# Temp_Sensor.net
KiCad netlist of a schematic drawn in EAGLE
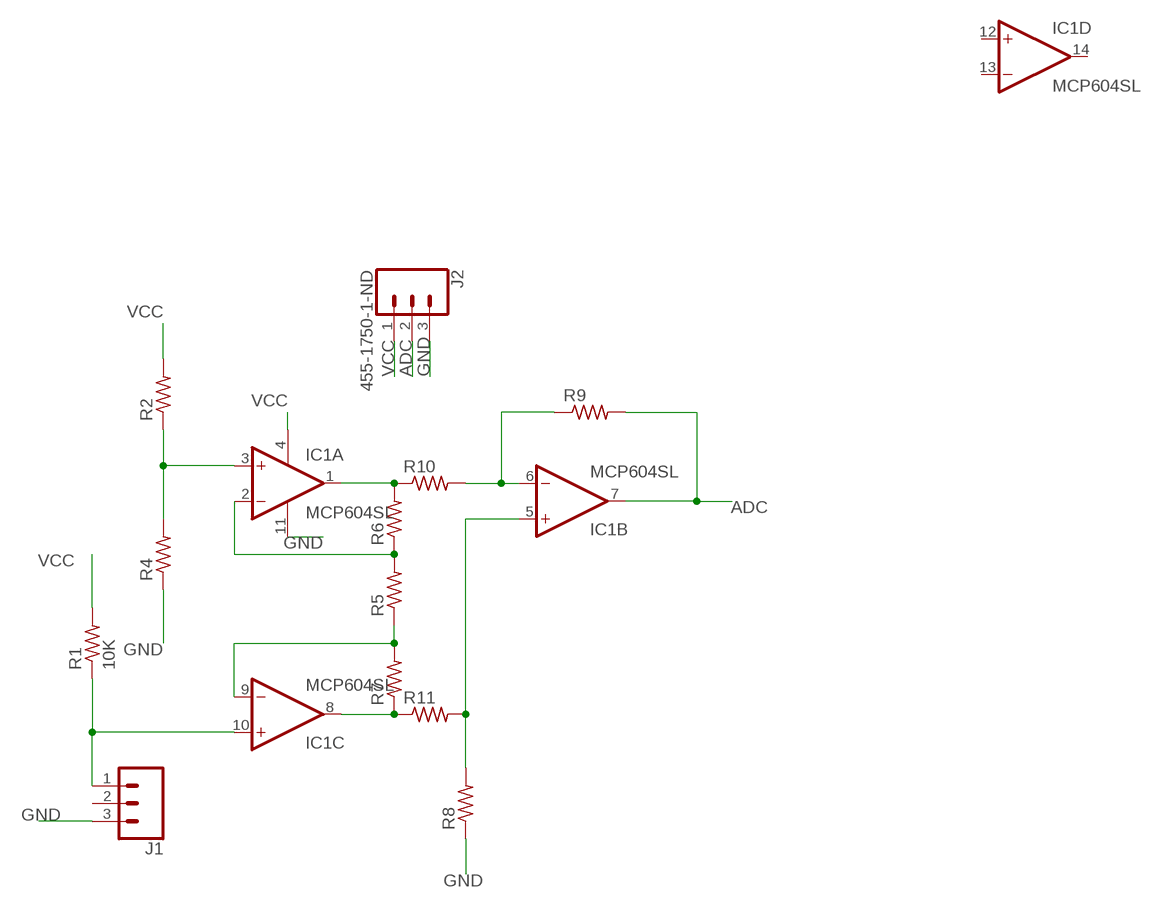
[diagram p0: schematic, sheet 1]

(export (version "E")
  (design (tool "Eeschema 10.0.6"))
  (components
    (comp (ref "IC1")
      (value "MCP604SL")
      (footprint "eagle-import:SO14")
      (libsource (lib "eagle-import") (part "MCP604SL"))
    )
    (comp (ref "J1")
      (value "CONN_03SCREW_LOCK")
      (footprint "eagle-import:SCREWTERMINAL-3.5MM-3_LOCK.007S")
      (libsource (lib "eagle-import") (part "CONN_03SCREW_LOCK"))
    )
    (comp (ref "J2")
      (value "455-1750-1-ND")
      (footprint "eagle-import:1X03")
      (libsource (lib "eagle-import") (part "CONN_03"))
    )
    (comp (ref "R1")
      (value "10K")
      (footprint "eagle-import:R0603")
      (libsource (lib "eagle-import") (part "R-US_R0603"))
    )
    (comp (ref "R2")
      (value "R-US_R0603")
      (footprint "eagle-import:R0603")
      (libsource (lib "eagle-import") (part "R-US_R0603"))
    )
    (comp (ref "R4")
      (value "R-US_R0603")
      (footprint "eagle-import:R0603")
      (libsource (lib "eagle-import") (part "R-US_R0603"))
    )
    (comp (ref "R5")
      (value "R-US_R0603")
      (footprint "eagle-import:R0603")
      (libsource (lib "eagle-import") (part "R-US_R0603"))
    )
    (comp (ref "R6")
      (value "R-US_R0603")
      (footprint "eagle-import:R0603")
      (libsource (lib "eagle-import") (part "R-US_R0603"))
    )
    (comp (ref "R7")
      (value "R-US_R0603")
      (footprint "eagle-import:R0603")
      (libsource (lib "eagle-import") (part "R-US_R0603"))
    )
    (comp (ref "R8")
      (value "R-US_R0603")
      (footprint "eagle-import:R0603")
      (libsource (lib "eagle-import") (part "R-US_R0603"))
    )
    (comp (ref "R9")
      (value "R-US_R0603")
      (footprint "eagle-import:R0603")
      (libsource (lib "eagle-import") (part "R-US_R0603"))
    )
    (comp (ref "R10")
      (value "R-US_R0603")
      (footprint "eagle-import:R0603")
      (libsource (lib "eagle-import") (part "R-US_R0603"))
    )
    (comp (ref "R11")
      (value "R-US_R0603")
      (footprint "eagle-import:R0603")
      (libsource (lib "eagle-import") (part "R-US_R0603"))
    )
  )
  (nets
    (net (code "1") (name "/ADC") (class "Default")
      (node (ref "IC1") (pin "7") (pinfunction "OUT_7") (pintype "output"))
      (node (ref "J2") (pin "2") (pinfunction "2_2") (pintype "passive"))
      (node (ref "R9") (pin "2") (pinfunction "2_2") (pintype "passive"))
    )
    (net (code "2") (name "/GND") (class "Default")
      (node (ref "IC1") (pin "11") (pinfunction "V-_11") (pintype "power_in"))
      (node (ref "J1") (pin "3") (pinfunction "3_3") (pintype "passive"))
      (node (ref "J2") (pin "3") (pinfunction "3_3") (pintype "passive"))
      (node (ref "R4") (pin "1") (pinfunction "1_1") (pintype "passive"))
      (node (ref "R8") (pin "1") (pinfunction "1_1") (pintype "passive"))
    )
    (net (code "3") (name "/VCC") (class "Default")
      (node (ref "IC1") (pin "4") (pinfunction "V+_4") (pintype "power_in"))
      (node (ref "J2") (pin "1") (pinfunction "1_1") (pintype "passive"))
      (node (ref "R1") (pin "2") (pinfunction "2_2") (pintype "passive"))
      (node (ref "R2") (pin "2") (pinfunction "2_2") (pintype "passive"))
    )
    (net (code "4") (name "Net-(IC1A-+IN)") (class "Default")
      (node (ref "IC1") (pin "3") (pinfunction "+IN_3") (pintype "input"))
      (node (ref "R2") (pin "1") (pinfunction "1_1") (pintype "passive"))
      (node (ref "R4") (pin "2") (pinfunction "2_2") (pintype "passive"))
    )
    (net (code "5") (name "Net-(IC1A--IN)") (class "Default")
      (node (ref "IC1") (pin "2") (pinfunction "-IN_2") (pintype "input"))
      (node (ref "R5") (pin "2") (pinfunction "2_2") (pintype "passive"))
      (node (ref "R6") (pin "1") (pinfunction "1_1") (pintype "passive"))
    )
    (net (code "6") (name "Net-(IC1A-OUT)") (class "Default")
      (node (ref "IC1") (pin "1") (pinfunction "OUT_1") (pintype "output"))
      (node (ref "R10") (pin "1") (pinfunction "1_1") (pintype "passive"))
      (node (ref "R6") (pin "2") (pinfunction "2_2") (pintype "passive"))
    )
    (net (code "7") (name "Net-(IC1B-+IN)") (class "Default")
      (node (ref "IC1") (pin "5") (pinfunction "+IN_5") (pintype "input"))
      (node (ref "R11") (pin "2") (pinfunction "2_2") (pintype "passive"))
      (node (ref "R8") (pin "2") (pinfunction "2_2") (pintype "passive"))
    )
    (net (code "8") (name "Net-(IC1B--IN)") (class "Default")
      (node (ref "IC1") (pin "6") (pinfunction "-IN_6") (pintype "input"))
      (node (ref "R10") (pin "2") (pinfunction "2_2") (pintype "passive"))
      (node (ref "R9") (pin "1") (pinfunction "1_1") (pintype "passive"))
    )
    (net (code "9") (name "Net-(IC1C-+IN)") (class "Default")
      (node (ref "IC1") (pin "10") (pinfunction "+IN_10") (pintype "input"))
      (node (ref "J1") (pin "1") (pinfunction "1_1") (pintype "passive"))
      (node (ref "R1") (pin "1") (pinfunction "1_1") (pintype "passive"))
    )
    (net (code "10") (name "Net-(IC1C--IN)") (class "Default")
      (node (ref "IC1") (pin "9") (pinfunction "-IN_9") (pintype "input"))
      (node (ref "R5") (pin "1") (pinfunction "1_1") (pintype "passive"))
      (node (ref "R7") (pin "2") (pinfunction "2_2") (pintype "passive"))
    )
    (net (code "11") (name "Net-(IC1C-OUT)") (class "Default")
      (node (ref "IC1") (pin "8") (pinfunction "OUT_8") (pintype "output"))
      (node (ref "R11") (pin "1") (pinfunction "1_1") (pintype "passive"))
      (node (ref "R7") (pin "1") (pinfunction "1_1") (pintype "passive"))
    )
    (net (code "12") (name "unconnected-(IC1D-+IN-Pad12)") (class "Default")
      (node (ref "IC1") (pin "12") (pinfunction "+IN_12") (pintype "input"))
    )
    (net (code "13") (name "unconnected-(IC1D--IN-Pad13)") (class "Default")
      (node (ref "IC1") (pin "13") (pinfunction "-IN_13") (pintype "input"))
    )
    (net (code "14") (name "unconnected-(IC1D-OUT-Pad14)") (class "Default")
      (node (ref "IC1") (pin "14") (pinfunction "OUT_14") (pintype "output"))
    )
    (net (code "15") (name "unconnected-(J1-Pad2)") (class "Default")
      (node (ref "J1") (pin "2") (pinfunction "2_2") (pintype "passive"))
    )
  )
)
